# example-bjt-circuits.net
KiCad netlist of a schematic drawn in EAGLE
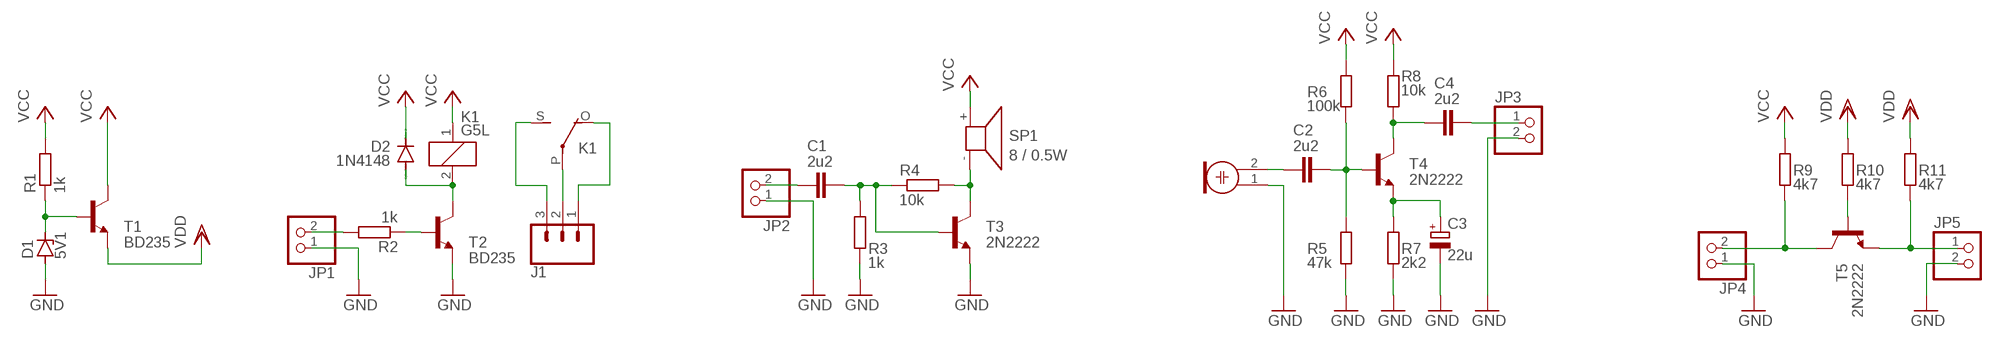
[diagram p0: schematic, sheet 1]

(export (version "E")
  (design (tool "Eeschema 10.0.6"))
  (components
    (comp (ref "C1")
      (value "2u2")
      (footprint "eagle-import:C025-030X050")
      (libsource (lib "eagle-import") (part "C-EU025-030X050"))
    )
    (comp (ref "C2")
      (value "2u2")
      (footprint "eagle-import:C025-030X050")
      (libsource (lib "eagle-import") (part "C-EU025-030X050"))
    )
    (comp (ref "C3")
      (value "22u")
      (footprint "eagle-import:E2,5-5")
      (libsource (lib "eagle-import") (part "CPOL-EUE2.5-5"))
    )
    (comp (ref "C4")
      (value "2u2")
      (footprint "eagle-import:C025-030X050")
      (libsource (lib "eagle-import") (part "C-EU025-030X050"))
    )
    (comp (ref "D1")
      (value "5V1")
      (footprint "eagle-import:C1702-15")
      (libsource (lib "eagle-import") (part "ZENER-DIODEC1702-15"))
    )
    (comp (ref "D2")
      (value "1N4148")
      (footprint "eagle-import:DO35-10")
      (libsource (lib "eagle-import") (part "1N4148DO35-10"))
    )
    (comp (ref "J1")
      (value "CONN_03SCREW-NS")
      (footprint "eagle-import:SCREWTERMINAL-3.5MM-3-NS")
      (libsource (lib "eagle-import") (part "CONN_03SCREW-NS"))
    )
    (comp (ref "JP1")
      (value "PINHD-1X2")
      (footprint "eagle-import:1X02")
      (libsource (lib "eagle-import") (part "PINHD-1X2"))
    )
    (comp (ref "JP2")
      (value "PINHD-1X2")
      (footprint "eagle-import:1X02")
      (libsource (lib "eagle-import") (part "PINHD-1X2"))
    )
    (comp (ref "JP3")
      (value "PINHD-1X2")
      (footprint "eagle-import:1X02")
      (libsource (lib "eagle-import") (part "PINHD-1X2"))
    )
    (comp (ref "JP4")
      (value "PINHD-1X2")
      (footprint "eagle-import:1X02")
      (libsource (lib "eagle-import") (part "PINHD-1X2"))
    )
    (comp (ref "JP5")
      (value "PINHD-1X2")
      (footprint "eagle-import:1X02")
      (libsource (lib "eagle-import") (part "PINHD-1X2"))
    )
    (comp (ref "K1")
      (value "G5L")
      (footprint "eagle-import:G5LE")
      (libsource (lib "eagle-import") (part "G5L"))
    )
    (comp (ref "M1")
      (value "ELECTRET_MICROPHON-WM.64PN")
      (footprint "eagle-import:WM-64PN")
      (libsource (lib "eagle-import") (part "ELECTRET_MICROPHON-WM.64PN"))
    )
    (comp (ref "R1")
      (value "1k")
      (footprint "eagle-import:0207_10")
      (libsource (lib "eagle-import") (part "R-EU_0207/10"))
    )
    (comp (ref "R2")
      (value "1k")
      (footprint "eagle-import:0207_10")
      (libsource (lib "eagle-import") (part "R-EU_0207/10"))
    )
    (comp (ref "R3")
      (value "1k")
      (footprint "eagle-import:0207_10")
      (libsource (lib "eagle-import") (part "R-EU_0207/10"))
    )
    (comp (ref "R4")
      (value "10k")
      (footprint "eagle-import:0207_10")
      (libsource (lib "eagle-import") (part "R-EU_0207/10"))
    )
    (comp (ref "R5")
      (value "47k")
      (footprint "eagle-import:0207_10")
      (libsource (lib "eagle-import") (part "R-EU_0207/10"))
    )
    (comp (ref "R6")
      (value "100k")
      (footprint "eagle-import:0207_10")
      (libsource (lib "eagle-import") (part "R-EU_0207/10"))
    )
    (comp (ref "R7")
      (value "2k2")
      (footprint "eagle-import:0207_10")
      (libsource (lib "eagle-import") (part "R-EU_0207/10"))
    )
    (comp (ref "R8")
      (value "10k")
      (footprint "eagle-import:0207_10")
      (libsource (lib "eagle-import") (part "R-EU_0207/10"))
    )
    (comp (ref "R9")
      (value "4k7")
      (footprint "eagle-import:0207_10")
      (libsource (lib "eagle-import") (part "R-EU_0207/10"))
    )
    (comp (ref "R10")
      (value "4k7")
      (footprint "eagle-import:0207_10")
      (libsource (lib "eagle-import") (part "R-EU_0207/10"))
    )
    (comp (ref "R11")
      (value "4k7")
      (footprint "eagle-import:0207_10")
      (libsource (lib "eagle-import") (part "R-EU_0207/10"))
    )
    (comp (ref "SP1")
      (value "8 / 0.5W")
      (footprint "eagle-import:AL11P")
      (libsource (lib "eagle-import") (part "AL11P"))
    )
    (comp (ref "T1")
      (value "BD235")
      (footprint "eagle-import:TO126")
      (libsource (lib "eagle-import") (part "BD235"))
    )
    (comp (ref "T2")
      (value "BD235")
      (footprint "eagle-import:TO126")
      (libsource (lib "eagle-import") (part "BD235"))
    )
    (comp (ref "T3")
      (value "2N2222")
      (footprint "eagle-import:TO18")
      (libsource (lib "eagle-import") (part "2N2222"))
    )
    (comp (ref "T4")
      (value "2N2222")
      (footprint "eagle-import:TO18")
      (libsource (lib "eagle-import") (part "2N2222"))
    )
    (comp (ref "T5")
      (value "2N2222")
      (footprint "eagle-import:TO18")
      (libsource (lib "eagle-import") (part "2N2222"))
    )
  )
  (nets
    (net (code "1") (name "GND") (class "Default")
      (node (ref "C3") (pin "-") (pinfunction "-_-") (pintype "passive"))
      (node (ref "D1") (pin "A") (pinfunction "A_A") (pintype "passive"))
      (node (ref "JP1") (pin "1") (pinfunction "1_1") (pintype "passive"))
      (node (ref "JP2") (pin "1") (pinfunction "1_1") (pintype "passive"))
      (node (ref "JP3") (pin "2") (pinfunction "2_2") (pintype "passive"))
      (node (ref "JP4") (pin "1") (pinfunction "1_1") (pintype "passive"))
      (node (ref "JP5") (pin "2") (pinfunction "2_2") (pintype "passive"))
      (node (ref "M1") (pin "1") (pinfunction "1_1") (pintype "passive"))
      (node (ref "R3") (pin "2") (pinfunction "2_2") (pintype "passive"))
      (node (ref "R5") (pin "1") (pinfunction "1_1") (pintype "passive"))
      (node (ref "R7") (pin "1") (pinfunction "1_1") (pintype "passive"))
      (node (ref "T2") (pin "1") (pinfunction "E_1") (pintype "passive"))
      (node (ref "T3") (pin "1") (pinfunction "E_1") (pintype "passive"))
    )
    (net (code "2") (name "Net-(C1-Pad1)") (class "Default")
      (node (ref "C1") (pin "1") (pinfunction "1_1") (pintype "passive"))
      (node (ref "JP2") (pin "2") (pinfunction "2_2") (pintype "passive"))
    )
    (net (code "3") (name "Net-(C2-Pad1)") (class "Default")
      (node (ref "C2") (pin "1") (pinfunction "1_1") (pintype "passive"))
      (node (ref "M1") (pin "2") (pinfunction "2_2") (pintype "passive"))
    )
    (net (code "4") (name "Net-(C4-Pad2)") (class "Default")
      (node (ref "C4") (pin "2") (pinfunction "2_2") (pintype "passive"))
      (node (ref "JP3") (pin "1") (pinfunction "1_1") (pintype "passive"))
    )
    (net (code "5") (name "Net-(J1-Pad1)") (class "Default")
      (node (ref "J1") (pin "1") (pinfunction "1_1") (pintype "passive"))
      (node (ref "K1") (pin "O") (pinfunction "O_O") (pintype "passive"))
    )
    (net (code "6") (name "Net-(J1-Pad2)") (class "Default")
      (node (ref "J1") (pin "2") (pinfunction "2_2") (pintype "passive"))
      (node (ref "K1") (pin "P") (pinfunction "P_P") (pintype "passive"))
    )
    (net (code "7") (name "Net-(J1-Pad3)") (class "Default")
      (node (ref "J1") (pin "3") (pinfunction "3_3") (pintype "passive"))
      (node (ref "K1") (pin "S") (pinfunction "S_S") (pintype "passive"))
    )
    (net (code "8") (name "Net-(JP1-Pad2)") (class "Default")
      (node (ref "JP1") (pin "2") (pinfunction "2_2") (pintype "passive"))
      (node (ref "R2") (pin "2") (pinfunction "2_2") (pintype "passive"))
    )
    (net (code "9") (name "Net-(SP1-1)") (class "Default")
      (node (ref "R4") (pin "2") (pinfunction "2_2") (pintype "passive"))
      (node (ref "SP1") (pin "-") (pinfunction "1_-") (pintype "passive"))
      (node (ref "T3") (pin "3") (pinfunction "C_3") (pintype "passive"))
    )
    (net (code "10") (name "Net-(T1-B)") (class "Default")
      (node (ref "D1") (pin "C") (pinfunction "C_C") (pintype "passive"))
      (node (ref "R1") (pin "1") (pinfunction "1_1") (pintype "passive"))
      (node (ref "T1") (pin "3") (pinfunction "B_3") (pintype "passive"))
    )
    (net (code "11") (name "Net-(T2-B)") (class "Default")
      (node (ref "R2") (pin "1") (pinfunction "1_1") (pintype "passive"))
      (node (ref "T2") (pin "3") (pinfunction "B_3") (pintype "passive"))
    )
    (net (code "12") (name "Net-(T2-C)") (class "Default")
      (node (ref "D2") (pin "A") (pinfunction "A_A") (pintype "passive"))
      (node (ref "K1") (pin "2") (pinfunction "2_2") (pintype "passive"))
      (node (ref "T2") (pin "2") (pinfunction "C_2") (pintype "passive"))
    )
    (net (code "13") (name "Net-(T3-B)") (class "Default")
      (node (ref "C1") (pin "2") (pinfunction "2_2") (pintype "passive"))
      (node (ref "R3") (pin "1") (pinfunction "1_1") (pintype "passive"))
      (node (ref "R4") (pin "1") (pinfunction "1_1") (pintype "passive"))
      (node (ref "T3") (pin "2") (pinfunction "B_2") (pintype "passive"))
    )
    (net (code "14") (name "Net-(T4-B)") (class "Default")
      (node (ref "C2") (pin "2") (pinfunction "2_2") (pintype "passive"))
      (node (ref "R5") (pin "2") (pinfunction "2_2") (pintype "passive"))
      (node (ref "R6") (pin "1") (pinfunction "1_1") (pintype "passive"))
      (node (ref "T4") (pin "2") (pinfunction "B_2") (pintype "passive"))
    )
    (net (code "15") (name "Net-(T4-C)") (class "Default")
      (node (ref "C4") (pin "1") (pinfunction "1_1") (pintype "passive"))
      (node (ref "R8") (pin "1") (pinfunction "1_1") (pintype "passive"))
      (node (ref "T4") (pin "3") (pinfunction "C_3") (pintype "passive"))
    )
    (net (code "16") (name "Net-(T4-E)") (class "Default")
      (node (ref "C3") (pin "+") (pinfunction "+_+") (pintype "passive"))
      (node (ref "R7") (pin "2") (pinfunction "2_2") (pintype "passive"))
      (node (ref "T4") (pin "1") (pinfunction "E_1") (pintype "passive"))
    )
    (net (code "17") (name "Net-(T5-B)") (class "Default")
      (node (ref "R10") (pin "1") (pinfunction "1_1") (pintype "passive"))
      (node (ref "T5") (pin "2") (pinfunction "B_2") (pintype "passive"))
    )
    (net (code "18") (name "Net-(T5-C)") (class "Default")
      (node (ref "JP4") (pin "2") (pinfunction "2_2") (pintype "passive"))
      (node (ref "R9") (pin "1") (pinfunction "1_1") (pintype "passive"))
      (node (ref "T5") (pin "3") (pinfunction "C_3") (pintype "passive"))
    )
    (net (code "19") (name "Net-(T5-E)") (class "Default")
      (node (ref "JP5") (pin "1") (pinfunction "1_1") (pintype "passive"))
      (node (ref "R11") (pin "1") (pinfunction "1_1") (pintype "passive"))
      (node (ref "T5") (pin "1") (pinfunction "E_1") (pintype "passive"))
    )
    (net (code "20") (name "VCC") (class "Default")
      (node (ref "D2") (pin "C") (pinfunction "C_C") (pintype "passive"))
      (node (ref "K1") (pin "1") (pinfunction "1_1") (pintype "passive"))
      (node (ref "R1") (pin "2") (pinfunction "2_2") (pintype "passive"))
      (node (ref "R6") (pin "2") (pinfunction "2_2") (pintype "passive"))
      (node (ref "R8") (pin "2") (pinfunction "2_2") (pintype "passive"))
      (node (ref "R9") (pin "2") (pinfunction "2_2") (pintype "passive"))
      (node (ref "SP1") (pin "+") (pinfunction "2_+") (pintype "passive"))
      (node (ref "T1") (pin "2") (pinfunction "C_2") (pintype "passive"))
    )
    (net (code "21") (name "VDD") (class "Default")
      (node (ref "R10") (pin "2") (pinfunction "2_2") (pintype "passive"))
      (node (ref "R11") (pin "2") (pinfunction "2_2") (pintype "passive"))
      (node (ref "T1") (pin "1") (pinfunction "E_1") (pintype "passive"))
    )
  )
)
